# CrackberryPi_1_0_5_test3.net
KiCad netlist of a schematic drawn in EAGLE
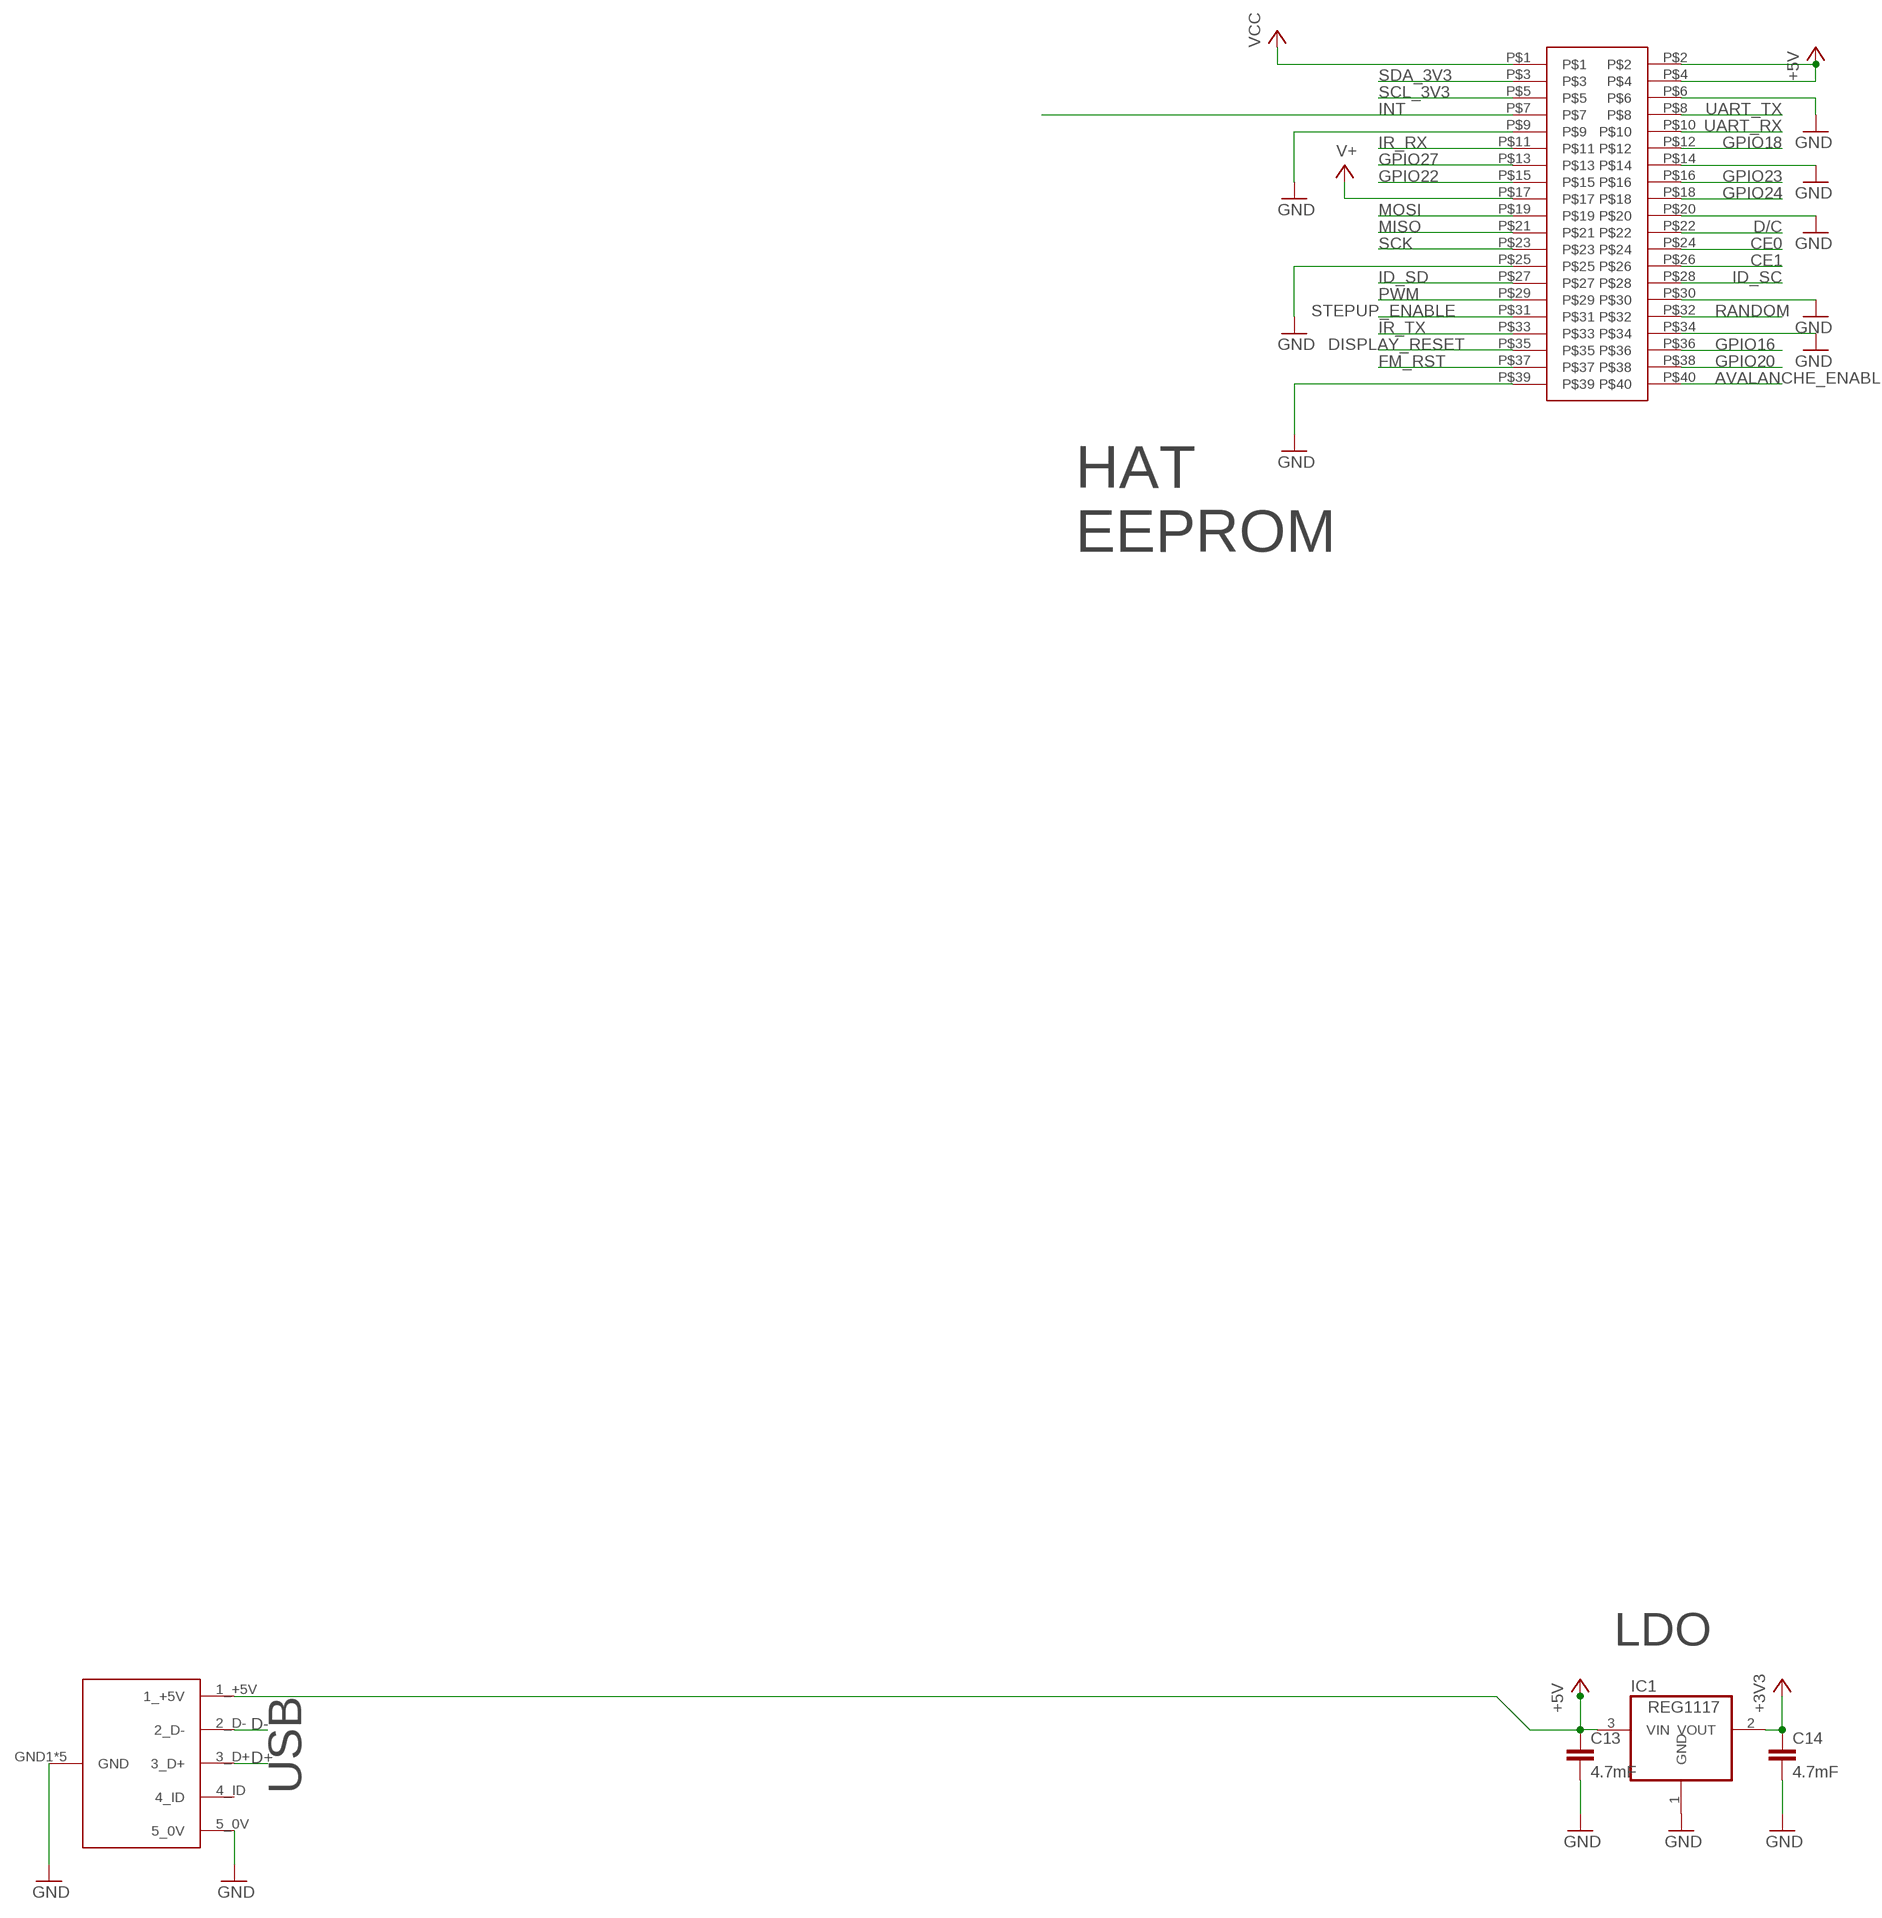
[diagram p0: schematic, sheet 1, part 1 of 2]
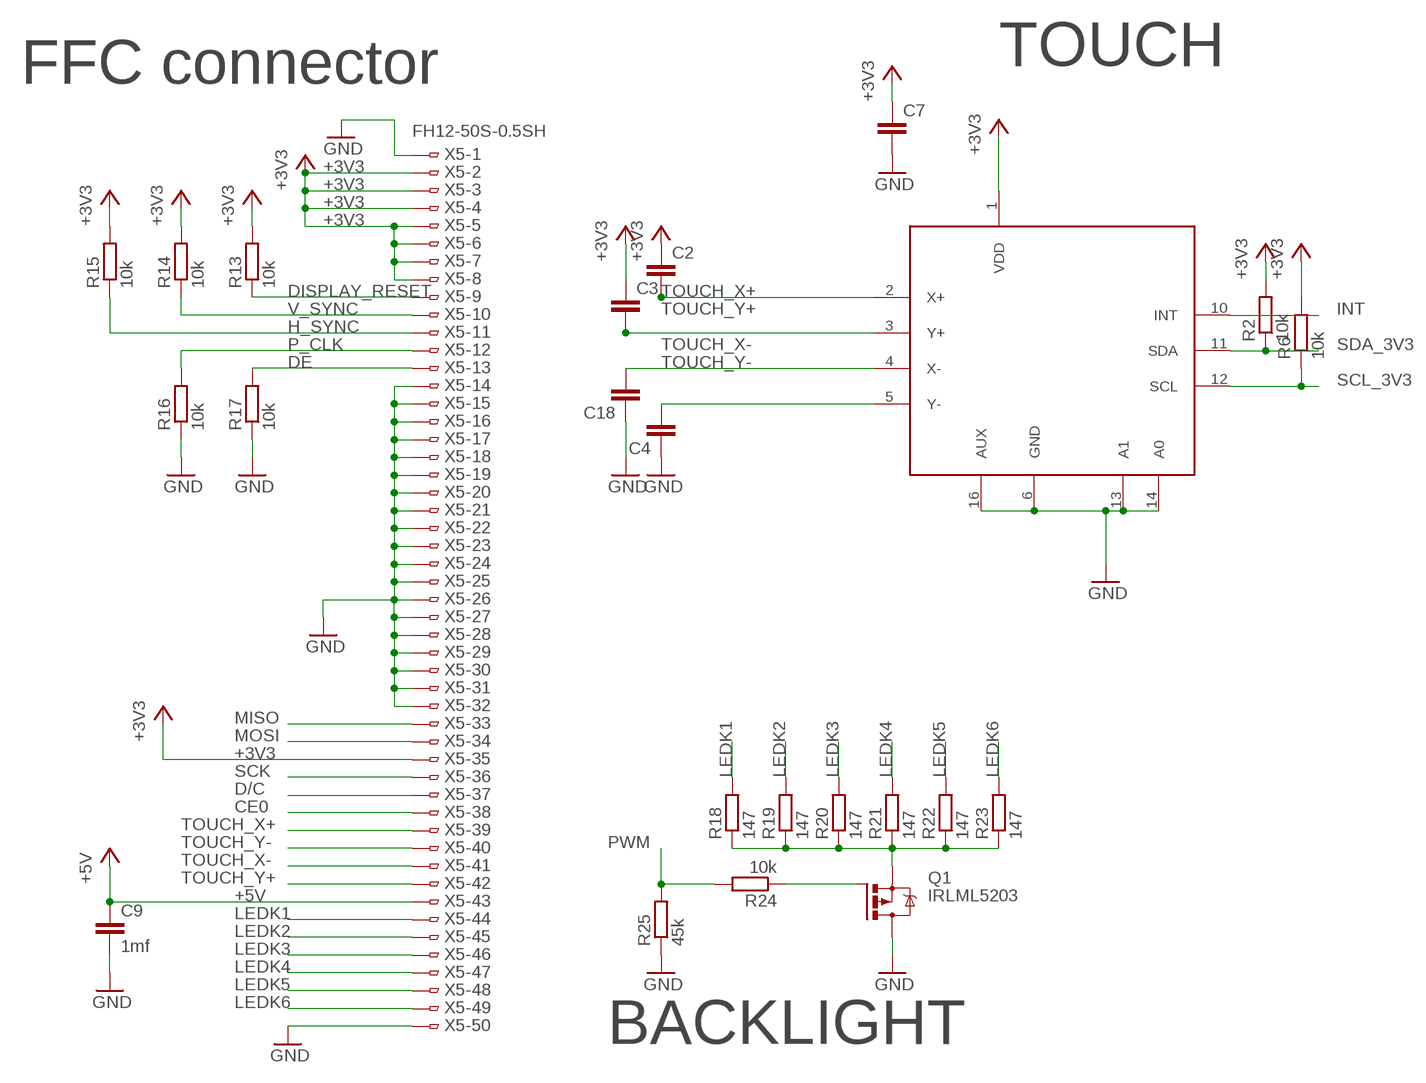
[diagram p1: schematic, sheet 1, part 2 of 2]

(export (version "E")
  (design (tool "Eeschema 10.0.6"))
  (components
    (comp (ref "C2")
      (value "C-EUC0603")
      (footprint "eagle-import:C0603")
      (libsource (lib "eagle-import") (part "C-EUC0603"))
    )
    (comp (ref "C3")
      (value "C-EUC0603")
      (footprint "eagle-import:C0603")
      (libsource (lib "eagle-import") (part "C-EUC0603"))
    )
    (comp (ref "C4")
      (value "C-EUC0603")
      (footprint "eagle-import:C0603")
      (libsource (lib "eagle-import") (part "C-EUC0603"))
    )
    (comp (ref "C7")
      (value "C-EUC0603")
      (footprint "eagle-import:C0603")
      (libsource (lib "eagle-import") (part "C-EUC0603"))
    )
    (comp (ref "C9")
      (value "1mf")
      (footprint "eagle-import:C0603")
      (libsource (lib "eagle-import") (part "C-EUC0603"))
    )
    (comp (ref "C13")
      (value "4.7mF")
      (footprint "eagle-import:C0603")
      (libsource (lib "eagle-import") (part "C-EUC0603"))
    )
    (comp (ref "C14")
      (value "4.7mF")
      (footprint "eagle-import:C0603")
      (libsource (lib "eagle-import") (part "C-EUC0603"))
    )
    (comp (ref "C18")
      (value "C-EUC0603")
      (footprint "eagle-import:C0603")
      (libsource (lib "eagle-import") (part "C-EUC0603"))
    )
    (comp (ref "IC1")
      (value "REG1117")
      (footprint "eagle-import:SOT223")
      (libsource (lib "eagle-import") (part "REG1117"))
    )
    (comp (ref "Q1")
      (value "IRLML5203")
      (footprint "eagle-import:MICRO3")
      (libsource (lib "eagle-import") (part "IRLML5203"))
    )
    (comp (ref "R2")
      (value "10k")
      (footprint "eagle-import:R0603")
      (libsource (lib "eagle-import") (part "R-EU_R0603"))
    )
    (comp (ref "R6")
      (value "10k")
      (footprint "eagle-import:R0603")
      (libsource (lib "eagle-import") (part "R-EU_R0603"))
    )
    (comp (ref "R13")
      (value "10k")
      (footprint "eagle-import:R0603")
      (libsource (lib "eagle-import") (part "R-EU_R0603"))
    )
    (comp (ref "R14")
      (value "10k")
      (footprint "eagle-import:R0603")
      (libsource (lib "eagle-import") (part "R-EU_R0603"))
    )
    (comp (ref "R15")
      (value "10k")
      (footprint "eagle-import:R0603")
      (libsource (lib "eagle-import") (part "R-EU_R0603"))
    )
    (comp (ref "R16")
      (value "10k")
      (footprint "eagle-import:R0603")
      (libsource (lib "eagle-import") (part "R-EU_R0603"))
    )
    (comp (ref "R17")
      (value "10k")
      (footprint "eagle-import:R0603")
      (libsource (lib "eagle-import") (part "R-EU_R0603"))
    )
    (comp (ref "R18")
      (value "147")
      (footprint "eagle-import:R0603")
      (libsource (lib "eagle-import") (part "R-EU_R0603"))
    )
    (comp (ref "R19")
      (value "147")
      (footprint "eagle-import:R0603")
      (libsource (lib "eagle-import") (part "R-EU_R0603"))
    )
    (comp (ref "R20")
      (value "147")
      (footprint "eagle-import:R0603")
      (libsource (lib "eagle-import") (part "R-EU_R0603"))
    )
    (comp (ref "R21")
      (value "147")
      (footprint "eagle-import:R0603")
      (libsource (lib "eagle-import") (part "R-EU_R0603"))
    )
    (comp (ref "R22")
      (value "147")
      (footprint "eagle-import:R0603")
      (libsource (lib "eagle-import") (part "R-EU_R0603"))
    )
    (comp (ref "R23")
      (value "147")
      (footprint "eagle-import:R0603")
      (libsource (lib "eagle-import") (part "R-EU_R0603"))
    )
    (comp (ref "R24")
      (value "10k")
      (footprint "eagle-import:R0603")
      (libsource (lib "eagle-import") (part "R-EU_R0603"))
    )
    (comp (ref "R25")
      (value "45k")
      (footprint "eagle-import:R0603")
      (libsource (lib "eagle-import") (part "R-EU_R0603"))
    )
    (comp (ref "U$6")
      (value "TSC2007")
      (footprint "eagle-import:TSSOP16")
      (libsource (lib "eagle-import") (part "TSC2007"))
    )
    (comp (ref "U$9")
      (value "MICRO_USB")
      (footprint "eagle-import:MICRO_USB")
      (libsource (lib "eagle-import") (part "MICRO_USB"))
    )
    (comp (ref "U$11")
      (value "HEADER")
      (footprint "eagle-import:20X2")
      (libsource (lib "eagle-import") (part "HEADER"))
    )
    (comp (ref "X5")
      (value "FH12-50S-0.5SH")
      (footprint "eagle-import:FH12-50S-0.5SH")
      (fields (field (name "MPN") "FH12-50S-0.5SH(55)"))
      (libsource (lib "eagle-import") (part "FH12-50S-0.5SH"))
    )
  )
  (nets
    (net (code "1") (name "+3V3") (class "Default")
      (node (ref "C14") (pin "1") (pinfunction "1_1") (pintype "passive"))
      (node (ref "C2") (pin "1") (pinfunction "1_1") (pintype "passive"))
      (node (ref "C3") (pin "1") (pinfunction "1_1") (pintype "passive"))
      (node (ref "C7") (pin "1") (pinfunction "1_1") (pintype "passive"))
      (node (ref "IC1") (pin "2") (pinfunction "VOUT_2") (pintype "output"))
      (node (ref "R13") (pin "2") (pinfunction "2_2") (pintype "passive"))
      (node (ref "R14") (pin "2") (pinfunction "2_2") (pintype "passive"))
      (node (ref "R15") (pin "2") (pinfunction "2_2") (pintype "passive"))
      (node (ref "R2") (pin "2") (pinfunction "2_2") (pintype "passive"))
      (node (ref "R6") (pin "2") (pinfunction "2_2") (pintype "passive"))
      (node (ref "U$6") (pin "1") (pinfunction "VDD_1") (pintype "bidirectional"))
      (node (ref "X5") (pin "2") (pinfunction "1_2") (pintype "passive"))
      (node (ref "X5") (pin "3") (pinfunction "1_3") (pintype "passive"))
      (node (ref "X5") (pin "35") (pinfunction "1_35") (pintype "passive"))
      (node (ref "X5") (pin "4") (pinfunction "1_4") (pintype "passive"))
      (node (ref "X5") (pin "5") (pinfunction "1_5") (pintype "passive"))
      (node (ref "X5") (pin "6") (pinfunction "1_6") (pintype "passive"))
      (node (ref "X5") (pin "7") (pinfunction "1_7") (pintype "passive"))
      (node (ref "X5") (pin "8") (pinfunction "1_8") (pintype "passive"))
    )
    (net (code "2") (name "+5V") (class "Default")
      (node (ref "C13") (pin "1") (pinfunction "1_1") (pintype "passive"))
      (node (ref "C9") (pin "1") (pinfunction "1_1") (pintype "passive"))
      (node (ref "IC1") (pin "3") (pinfunction "VIN_3") (pintype "input"))
      (node (ref "U$11") (pin "P$2") (pinfunction "P$2_P$2") (pintype "bidirectional"))
      (node (ref "U$11") (pin "P$4") (pinfunction "P$4_P$4") (pintype "bidirectional"))
      (node (ref "U$9") (pin "1_+5V") (pinfunction "1_+5V_1_+5V") (pintype "bidirectional"))
      (node (ref "X5") (pin "43") (pinfunction "1_43") (pintype "passive"))
    )
    (net (code "3") (name "/AVALANCHE_ENABLE") (class "Default")
      (node (ref "U$11") (pin "P$40") (pinfunction "P$40_P$40") (pintype "bidirectional"))
    )
    (net (code "4") (name "/CE0") (class "Default")
      (node (ref "U$11") (pin "P$24") (pinfunction "P$24_P$24") (pintype "bidirectional"))
      (node (ref "X5") (pin "38") (pinfunction "1_38") (pintype "passive"))
    )
    (net (code "5") (name "/CE1") (class "Default")
      (node (ref "U$11") (pin "P$26") (pinfunction "P$26_P$26") (pintype "bidirectional"))
    )
    (net (code "6") (name "/D+") (class "Default")
      (node (ref "U$9") (pin "3_D+") (pinfunction "3_D+_3_D+") (pintype "bidirectional"))
    )
    (net (code "7") (name "/D-") (class "Default")
      (node (ref "U$9") (pin "2_D-") (pinfunction "2_D-_2_D-") (pintype "bidirectional"))
    )
    (net (code "8") (name "/DE") (class "Default")
      (node (ref "R17") (pin "2") (pinfunction "2_2") (pintype "passive"))
      (node (ref "X5") (pin "13") (pinfunction "1_13") (pintype "passive"))
    )
    (net (code "9") (name "/DISPLAY_RESET") (class "Default")
      (node (ref "R13") (pin "1") (pinfunction "1_1") (pintype "passive"))
      (node (ref "U$11") (pin "P$35") (pinfunction "P$35_P$35") (pintype "bidirectional"))
      (node (ref "X5") (pin "9") (pinfunction "1_9") (pintype "passive"))
    )
    (net (code "10") (name "/D{slash}C") (class "Default")
      (node (ref "U$11") (pin "P$22") (pinfunction "P$22_P$22") (pintype "bidirectional"))
      (node (ref "X5") (pin "37") (pinfunction "1_37") (pintype "passive"))
    )
    (net (code "11") (name "/FM_RST") (class "Default")
      (node (ref "U$11") (pin "P$37") (pinfunction "P$37_P$37") (pintype "bidirectional"))
    )
    (net (code "12") (name "/GPIO16") (class "Default")
      (node (ref "U$11") (pin "P$36") (pinfunction "P$36_P$36") (pintype "bidirectional"))
    )
    (net (code "13") (name "/GPIO18") (class "Default")
      (node (ref "U$11") (pin "P$12") (pinfunction "P$12_P$12") (pintype "bidirectional"))
    )
    (net (code "14") (name "/GPIO20") (class "Default")
      (node (ref "U$11") (pin "P$38") (pinfunction "P$38_P$38") (pintype "bidirectional"))
    )
    (net (code "15") (name "/GPIO22") (class "Default")
      (node (ref "U$11") (pin "P$15") (pinfunction "P$15_P$15") (pintype "bidirectional"))
    )
    (net (code "16") (name "/GPIO23") (class "Default")
      (node (ref "U$11") (pin "P$16") (pinfunction "P$16_P$16") (pintype "bidirectional"))
    )
    (net (code "17") (name "/GPIO24") (class "Default")
      (node (ref "U$11") (pin "P$18") (pinfunction "P$18_P$18") (pintype "bidirectional"))
    )
    (net (code "18") (name "/GPIO27") (class "Default")
      (node (ref "U$11") (pin "P$13") (pinfunction "P$13_P$13") (pintype "bidirectional"))
    )
    (net (code "19") (name "/H_SYNC") (class "Default")
      (node (ref "R15") (pin "1") (pinfunction "1_1") (pintype "passive"))
      (node (ref "X5") (pin "11") (pinfunction "1_11") (pintype "passive"))
    )
    (net (code "20") (name "/ID_SC") (class "Default")
      (node (ref "U$11") (pin "P$28") (pinfunction "P$28_P$28") (pintype "bidirectional"))
    )
    (net (code "21") (name "/ID_SD") (class "Default")
      (node (ref "U$11") (pin "P$27") (pinfunction "P$27_P$27") (pintype "bidirectional"))
    )
    (net (code "22") (name "/INT") (class "Default")
      (node (ref "U$11") (pin "P$7") (pinfunction "P$7_P$7") (pintype "bidirectional"))
      (node (ref "U$6") (pin "10") (pinfunction "INT_10") (pintype "bidirectional"))
    )
    (net (code "23") (name "/IR_RX") (class "Default")
      (node (ref "U$11") (pin "P$11") (pinfunction "P$11_P$11") (pintype "bidirectional"))
    )
    (net (code "24") (name "/IR_TX") (class "Default")
      (node (ref "U$11") (pin "P$33") (pinfunction "P$33_P$33") (pintype "bidirectional"))
    )
    (net (code "25") (name "/LEDK1") (class "Default")
      (node (ref "R18") (pin "2") (pinfunction "2_2") (pintype "passive"))
      (node (ref "X5") (pin "44") (pinfunction "1_44") (pintype "passive"))
    )
    (net (code "26") (name "/LEDK2") (class "Default")
      (node (ref "R19") (pin "2") (pinfunction "2_2") (pintype "passive"))
      (node (ref "X5") (pin "45") (pinfunction "1_45") (pintype "passive"))
    )
    (net (code "27") (name "/LEDK3") (class "Default")
      (node (ref "R20") (pin "2") (pinfunction "2_2") (pintype "passive"))
      (node (ref "X5") (pin "46") (pinfunction "1_46") (pintype "passive"))
    )
    (net (code "28") (name "/LEDK4") (class "Default")
      (node (ref "R21") (pin "2") (pinfunction "2_2") (pintype "passive"))
      (node (ref "X5") (pin "47") (pinfunction "1_47") (pintype "passive"))
    )
    (net (code "29") (name "/LEDK5") (class "Default")
      (node (ref "R22") (pin "2") (pinfunction "2_2") (pintype "passive"))
      (node (ref "X5") (pin "48") (pinfunction "1_48") (pintype "passive"))
    )
    (net (code "30") (name "/LEDK6") (class "Default")
      (node (ref "R23") (pin "2") (pinfunction "2_2") (pintype "passive"))
      (node (ref "X5") (pin "49") (pinfunction "1_49") (pintype "passive"))
    )
    (net (code "31") (name "/MISO") (class "Default")
      (node (ref "U$11") (pin "P$21") (pinfunction "P$21_P$21") (pintype "bidirectional"))
      (node (ref "X5") (pin "33") (pinfunction "1_33") (pintype "passive"))
    )
    (net (code "32") (name "/MOSI") (class "Default")
      (node (ref "U$11") (pin "P$19") (pinfunction "P$19_P$19") (pintype "bidirectional"))
      (node (ref "X5") (pin "34") (pinfunction "1_34") (pintype "passive"))
    )
    (net (code "33") (name "/PWM") (class "Default")
      (node (ref "R24") (pin "2") (pinfunction "2_2") (pintype "passive"))
      (node (ref "R25") (pin "2") (pinfunction "2_2") (pintype "passive"))
      (node (ref "U$11") (pin "P$29") (pinfunction "P$29_P$29") (pintype "bidirectional"))
    )
    (net (code "34") (name "/P_CLK") (class "Default")
      (node (ref "R16") (pin "2") (pinfunction "2_2") (pintype "passive"))
      (node (ref "X5") (pin "12") (pinfunction "1_12") (pintype "passive"))
    )
    (net (code "35") (name "/RANDOM") (class "Default")
      (node (ref "U$11") (pin "P$32") (pinfunction "P$32_P$32") (pintype "bidirectional"))
    )
    (net (code "36") (name "/SCK") (class "Default")
      (node (ref "U$11") (pin "P$23") (pinfunction "P$23_P$23") (pintype "bidirectional"))
      (node (ref "X5") (pin "36") (pinfunction "1_36") (pintype "passive"))
    )
    (net (code "37") (name "/SCL_3V3") (class "Default")
      (node (ref "R6") (pin "1") (pinfunction "1_1") (pintype "passive"))
      (node (ref "U$11") (pin "P$5") (pinfunction "P$5_P$5") (pintype "bidirectional"))
      (node (ref "U$6") (pin "12") (pinfunction "SCL_12") (pintype "bidirectional"))
    )
    (net (code "38") (name "/SDA_3V3") (class "Default")
      (node (ref "R2") (pin "1") (pinfunction "1_1") (pintype "passive"))
      (node (ref "U$11") (pin "P$3") (pinfunction "P$3_P$3") (pintype "bidirectional"))
      (node (ref "U$6") (pin "11") (pinfunction "SDA_11") (pintype "bidirectional"))
    )
    (net (code "39") (name "/STEPUP_ENABLE") (class "Default")
      (node (ref "U$11") (pin "P$31") (pinfunction "P$31_P$31") (pintype "bidirectional"))
    )
    (net (code "40") (name "/TOUCH_X+") (class "Default")
      (node (ref "C2") (pin "2") (pinfunction "2_2") (pintype "passive"))
      (node (ref "U$6") (pin "2") (pinfunction "X+_2") (pintype "bidirectional"))
      (node (ref "X5") (pin "39") (pinfunction "1_39") (pintype "passive"))
    )
    (net (code "41") (name "/TOUCH_X-") (class "Default")
      (node (ref "C18") (pin "2") (pinfunction "2_2") (pintype "passive"))
      (node (ref "U$6") (pin "4") (pinfunction "X-_4") (pintype "bidirectional"))
      (node (ref "X5") (pin "41") (pinfunction "1_41") (pintype "passive"))
    )
    (net (code "42") (name "/TOUCH_Y+") (class "Default")
      (node (ref "C3") (pin "2") (pinfunction "2_2") (pintype "passive"))
      (node (ref "U$6") (pin "3") (pinfunction "Y+_3") (pintype "bidirectional"))
      (node (ref "X5") (pin "42") (pinfunction "1_42") (pintype "passive"))
    )
    (net (code "43") (name "/TOUCH_Y-") (class "Default")
      (node (ref "C4") (pin "2") (pinfunction "2_2") (pintype "passive"))
      (node (ref "U$6") (pin "5") (pinfunction "Y-_5") (pintype "bidirectional"))
      (node (ref "X5") (pin "40") (pinfunction "1_40") (pintype "passive"))
    )
    (net (code "44") (name "/UART_RX") (class "Default")
      (node (ref "U$11") (pin "P$10") (pinfunction "P$10_P$10") (pintype "bidirectional"))
    )
    (net (code "45") (name "/UART_TX") (class "Default")
      (node (ref "U$11") (pin "P$8") (pinfunction "P$8_P$8") (pintype "bidirectional"))
    )
    (net (code "46") (name "/V_SYNC") (class "Default")
      (node (ref "R14") (pin "1") (pinfunction "1_1") (pintype "passive"))
      (node (ref "X5") (pin "10") (pinfunction "1_10") (pintype "passive"))
    )
    (net (code "47") (name "GND") (class "Default")
      (node (ref "C13") (pin "2") (pinfunction "2_2") (pintype "passive"))
      (node (ref "C14") (pin "2") (pinfunction "2_2") (pintype "passive"))
      (node (ref "C18") (pin "1") (pinfunction "1_1") (pintype "passive"))
      (node (ref "C4") (pin "1") (pinfunction "1_1") (pintype "passive"))
      (node (ref "C7") (pin "2") (pinfunction "2_2") (pintype "passive"))
      (node (ref "C9") (pin "2") (pinfunction "2_2") (pintype "passive"))
      (node (ref "IC1") (pin "1") (pinfunction "GND_1") (pintype "power_in"))
      (node (ref "Q1") (pin "3") (pinfunction "D_3") (pintype "passive"))
      (node (ref "R16") (pin "1") (pinfunction "1_1") (pintype "passive"))
      (node (ref "R17") (pin "1") (pinfunction "1_1") (pintype "passive"))
      (node (ref "R25") (pin "1") (pinfunction "1_1") (pintype "passive"))
      (node (ref "U$11") (pin "P$14") (pinfunction "P$14_P$14") (pintype "bidirectional"))
      (node (ref "U$11") (pin "P$20") (pinfunction "P$20_P$20") (pintype "bidirectional"))
      (node (ref "U$11") (pin "P$25") (pinfunction "P$25_P$25") (pintype "bidirectional"))
      (node (ref "U$11") (pin "P$30") (pinfunction "P$30_P$30") (pintype "bidirectional"))
      (node (ref "U$11") (pin "P$34") (pinfunction "P$34_P$34") (pintype "bidirectional"))
      (node (ref "U$11") (pin "P$39") (pinfunction "P$39_P$39") (pintype "bidirectional"))
      (node (ref "U$11") (pin "P$6") (pinfunction "P$6_P$6") (pintype "bidirectional"))
      (node (ref "U$11") (pin "P$9") (pinfunction "P$9_P$9") (pintype "bidirectional"))
      (node (ref "U$6") (pin "13") (pinfunction "A1_13") (pintype "bidirectional"))
      (node (ref "U$6") (pin "14") (pinfunction "A0_14") (pintype "bidirectional"))
      (node (ref "U$6") (pin "16") (pinfunction "AUX_16") (pintype "bidirectional"))
      (node (ref "U$6") (pin "6") (pinfunction "GND_6") (pintype "bidirectional"))
      (node (ref "U$9") (pin "5_0V") (pinfunction "5_0V_5_0V") (pintype "bidirectional"))
      (node (ref "U$9") (pin "GND1") (pinfunction "GND_GND1") (pintype "bidirectional"))
      (node (ref "U$9") (pin "GND2") (pinfunction "GND_GND2") (pintype "bidirectional"))
      (node (ref "U$9") (pin "GND5") (pinfunction "GND_GND5") (pintype "bidirectional"))
      (node (ref "U$9") (pin "P$1") (pinfunction "GND_P$1") (pintype "bidirectional"))
      (node (ref "U$9") (pin "P$7") (pinfunction "GND_P$7") (pintype "bidirectional"))
      (node (ref "X5") (pin "1") (pinfunction "1_1") (pintype "passive"))
      (node (ref "X5") (pin "14") (pinfunction "1_14") (pintype "passive"))
      (node (ref "X5") (pin "15") (pinfunction "1_15") (pintype "passive"))
      (node (ref "X5") (pin "16") (pinfunction "1_16") (pintype "passive"))
      (node (ref "X5") (pin "17") (pinfunction "1_17") (pintype "passive"))
      (node (ref "X5") (pin "18") (pinfunction "1_18") (pintype "passive"))
      (node (ref "X5") (pin "19") (pinfunction "1_19") (pintype "passive"))
      (node (ref "X5") (pin "20") (pinfunction "1_20") (pintype "passive"))
      (node (ref "X5") (pin "21") (pinfunction "1_21") (pintype "passive"))
      (node (ref "X5") (pin "22") (pinfunction "1_22") (pintype "passive"))
      (node (ref "X5") (pin "23") (pinfunction "1_23") (pintype "passive"))
      (node (ref "X5") (pin "24") (pinfunction "1_24") (pintype "passive"))
      (node (ref "X5") (pin "25") (pinfunction "1_25") (pintype "passive"))
      (node (ref "X5") (pin "26") (pinfunction "1_26") (pintype "passive"))
      (node (ref "X5") (pin "27") (pinfunction "1_27") (pintype "passive"))
      (node (ref "X5") (pin "28") (pinfunction "1_28") (pintype "passive"))
      (node (ref "X5") (pin "29") (pinfunction "1_29") (pintype "passive"))
      (node (ref "X5") (pin "30") (pinfunction "1_30") (pintype "passive"))
      (node (ref "X5") (pin "31") (pinfunction "1_31") (pintype "passive"))
      (node (ref "X5") (pin "32") (pinfunction "1_32") (pintype "passive"))
      (node (ref "X5") (pin "50") (pinfunction "1_50") (pintype "passive"))
    )
    (net (code "48") (name "Net-(Q1-G)") (class "Default")
      (node (ref "Q1") (pin "1") (pinfunction "G_1") (pintype "passive"))
      (node (ref "R24") (pin "1") (pinfunction "1_1") (pintype "passive"))
    )
    (net (code "49") (name "Net-(Q1-S)") (class "Default")
      (node (ref "Q1") (pin "2") (pinfunction "S_2") (pintype "passive"))
      (node (ref "R18") (pin "1") (pinfunction "1_1") (pintype "passive"))
      (node (ref "R19") (pin "1") (pinfunction "1_1") (pintype "passive"))
      (node (ref "R20") (pin "1") (pinfunction "1_1") (pintype "passive"))
      (node (ref "R21") (pin "1") (pinfunction "1_1") (pintype "passive"))
      (node (ref "R22") (pin "1") (pinfunction "1_1") (pintype "passive"))
      (node (ref "R23") (pin "1") (pinfunction "1_1") (pintype "passive"))
    )
    (net (code "50") (name "V+") (class "Default")
      (node (ref "U$11") (pin "P$17") (pinfunction "P$17_P$17") (pintype "bidirectional"))
    )
    (net (code "51") (name "VCC") (class "Default")
      (node (ref "U$11") (pin "P$1") (pinfunction "P$1_P$1") (pintype "bidirectional"))
    )
    (net (code "52") (name "unconnected-(U$9-Pad4_ID)") (class "Default")
      (node (ref "U$9") (pin "4_ID") (pinfunction "4_ID_4_ID") (pintype "bidirectional"))
    )
  )
)
